# Guide_laser.net
KiCad netlist of a schematic drawn in Altium Designer
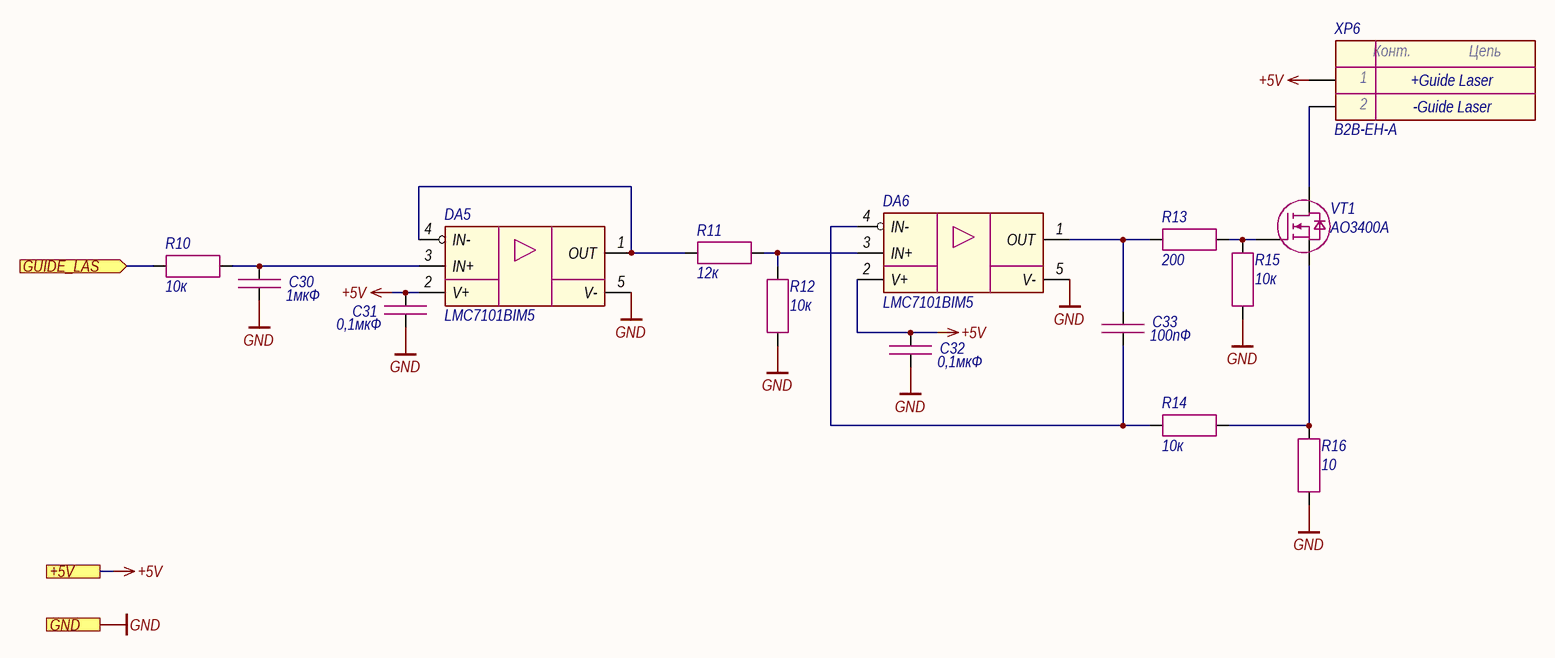
[diagram p0: Guide_laser.SchDoc]

(export (version "E")
  (design (tool "Eeschema 10.0.6"))
  (components
    (comp (ref "C30")
      (value "1мкФ")
      (footprint "Pcb_library:CAP_0603")
      (fields (field (name "MANUFACTURER") "Murata"))
      (libsource (lib "Schem_library") (part "Capacitor"))
    )
    (comp (ref "C31")
      (value "0,1мкФ")
      (footprint "Pcb_library:CAP_0603")
      (fields (field (name "MANUFACTURER") "Murata"))
      (libsource (lib "Schem_library") (part "Capacitor"))
    )
    (comp (ref "C32")
      (value "0,1мкФ")
      (footprint "Pcb_library:CAP_0603")
      (fields (field (name "MANUFACTURER") "Murata"))
      (libsource (lib "Schem_library") (part "Capacitor"))
    )
    (comp (ref "C33")
      (value "100пФ")
      (footprint "Pcb_library:CAP_0603")
      (fields (field (name "MANUFACTURER") "Murata"))
      (libsource (lib "Schem_library") (part "Capacitor"))
    )
    (comp (ref "DA5")
      (value "LMC7101BIM5")
      (footprint "Pcb_library:SOT-23-5")
      (fields (field (name "MANUFACTURER") "Texas Instruments"))
      (libsource (lib "Schem_library") (part "LMC7101"))
    )
    (comp (ref "DA6")
      (value "LMC7101BIM5")
      (footprint "Pcb_library:SOT-23-5")
      (fields (field (name "MANUFACTURER") "Texas Instruments"))
      (libsource (lib "Schem_library") (part "LMC7101"))
    )
    (comp (ref "R10")
      (value "10к")
      (footprint "Pcb_library:RES_0603")
      (fields (field (name "MANUFACTURER") "Yageo"))
      (libsource (lib "Schem_library") (part "Resistor"))
    )
    (comp (ref "R11")
      (value "12к")
      (footprint "Pcb_library:RES_0603")
      (fields (field (name "MANUFACTURER") "Yageo"))
      (libsource (lib "Schem_library") (part "Resistor"))
    )
    (comp (ref "R12")
      (value "10к")
      (footprint "Pcb_library:RES_0603")
      (fields (field (name "MANUFACTURER") "Yageo"))
      (libsource (lib "Schem_library") (part "Resistor"))
    )
    (comp (ref "R13")
      (value "200")
      (footprint "Pcb_library:RES_0603")
      (fields (field (name "MANUFACTURER") "Yageo"))
      (libsource (lib "Schem_library") (part "Resistor"))
    )
    (comp (ref "R14")
      (value "10к")
      (footprint "Pcb_library:RES_0603")
      (fields (field (name "MANUFACTURER") "Yageo"))
      (libsource (lib "Schem_library") (part "Resistor"))
    )
    (comp (ref "R15")
      (value "10к")
      (footprint "Pcb_library:RES_0603")
      (fields (field (name "MANUFACTURER") "Yageo"))
      (libsource (lib "Schem_library") (part "Resistor"))
    )
    (comp (ref "R16")
      (value "10")
      (footprint "Pcb_library:RES_1210")
      (fields (field (name "MANUFACTURER") "Yageo"))
      (libsource (lib "Schem_library") (part "Resistor"))
    )
    (comp (ref "VT1")
      (value "AO3400A")
      (footprint "Pcb_library:SOT-23-3")
      (fields (field (name "MANUFACTURER") "UMW"))
      (libsource (lib "Schem_library") (part "MOSFET N-channel"))
    )
    (comp (ref "XP6")
      (value "B2B-EH-A")
      (footprint "Pcb_library:B2B-EH-A")
      (fields (field (name "MANUFACTURER") "JST"))
      (libsource (lib "Schem_library") (part "Connector-2"))
    )
  )
  (nets
    (net (code "1") (name "+5V") (class "Default")
      (node (ref "C31") (pin "1") (pinfunction "1_1") (pintype "passive"))
      (node (ref "C32") (pin "1") (pinfunction "1_1") (pintype "passive"))
      (node (ref "DA5") (pin "2") (pinfunction "V+_2") (pintype "passive"))
      (node (ref "DA6") (pin "2") (pinfunction "V+_2") (pintype "passive"))
      (node (ref "XP6") (pin "1") (pintype "passive"))
    )
    (net (code "2") (name "/GUIDE_LAS") (class "Default")
      (node (ref "R10") (pin "1") (pinfunction "1_1") (pintype "passive"))
    )
    (net (code "3") (name "GND") (class "Default")
      (node (ref "C30") (pin "2") (pinfunction "2_2") (pintype "passive"))
      (node (ref "C31") (pin "2") (pinfunction "2_2") (pintype "passive"))
      (node (ref "C32") (pin "2") (pinfunction "2_2") (pintype "passive"))
      (node (ref "DA5") (pin "5") (pinfunction "V-_5") (pintype "passive"))
      (node (ref "DA6") (pin "5") (pinfunction "V-_5") (pintype "passive"))
      (node (ref "R12") (pin "2") (pinfunction "2_2") (pintype "passive"))
      (node (ref "R15") (pin "1") (pinfunction "1_1") (pintype "passive"))
      (node (ref "R16") (pin "1") (pinfunction "1_1") (pintype "passive"))
    )
    (net (code "4") (name "Net-(DA5-IN+)") (class "Default")
      (node (ref "C30") (pin "1") (pinfunction "1_1") (pintype "passive"))
      (node (ref "DA5") (pin "3") (pinfunction "IN+_3") (pintype "passive"))
      (node (ref "R10") (pin "2") (pinfunction "2_2") (pintype "passive"))
    )
    (net (code "5") (name "Net-(DA5-IN-)") (class "Default")
      (node (ref "DA5") (pin "1") (pinfunction "OUT_1") (pintype "passive"))
      (node (ref "DA5") (pin "4") (pinfunction "IN-_4") (pintype "passive"))
      (node (ref "R11") (pin "1") (pinfunction "1_1") (pintype "passive"))
    )
    (net (code "6") (name "Net-(DA6-IN+)") (class "Default")
      (node (ref "DA6") (pin "3") (pinfunction "IN+_3") (pintype "passive"))
      (node (ref "R11") (pin "2") (pinfunction "2_2") (pintype "passive"))
      (node (ref "R12") (pin "1") (pinfunction "1_1") (pintype "passive"))
    )
    (net (code "7") (name "Net-(DA6-IN-)") (class "Default")
      (node (ref "C33") (pin "2") (pinfunction "2_2") (pintype "passive"))
      (node (ref "DA6") (pin "4") (pinfunction "IN-_4") (pintype "passive"))
      (node (ref "R14") (pin "1") (pinfunction "1_1") (pintype "passive"))
    )
    (net (code "8") (name "Net-(DA6-OUT)") (class "Default")
      (node (ref "C33") (pin "1") (pinfunction "1_1") (pintype "passive"))
      (node (ref "DA6") (pin "1") (pinfunction "OUT_1") (pintype "passive"))
      (node (ref "R13") (pin "1") (pinfunction "1_1") (pintype "passive"))
    )
    (net (code "9") (name "Net-(VT1-D)") (class "Default")
      (node (ref "VT1") (pin "3") (pinfunction "D_3") (pintype "passive"))
      (node (ref "XP6") (pin "2") (pintype "passive"))
    )
    (net (code "10") (name "Net-(VT1-G)") (class "Default")
      (node (ref "R13") (pin "2") (pinfunction "2_2") (pintype "passive"))
      (node (ref "R15") (pin "2") (pinfunction "2_2") (pintype "passive"))
      (node (ref "VT1") (pin "1") (pinfunction "G_1") (pintype "passive"))
    )
    (net (code "11") (name "Net-(VT1-S)") (class "Default")
      (node (ref "R14") (pin "2") (pinfunction "2_2") (pintype "passive"))
      (node (ref "R16") (pin "2") (pinfunction "2_2") (pintype "passive"))
      (node (ref "VT1") (pin "2") (pinfunction "S_2") (pintype "passive"))
    )
  )
)
